# SMALL_BCM.net
KiCad netlist of a schematic drawn in Altium Designer
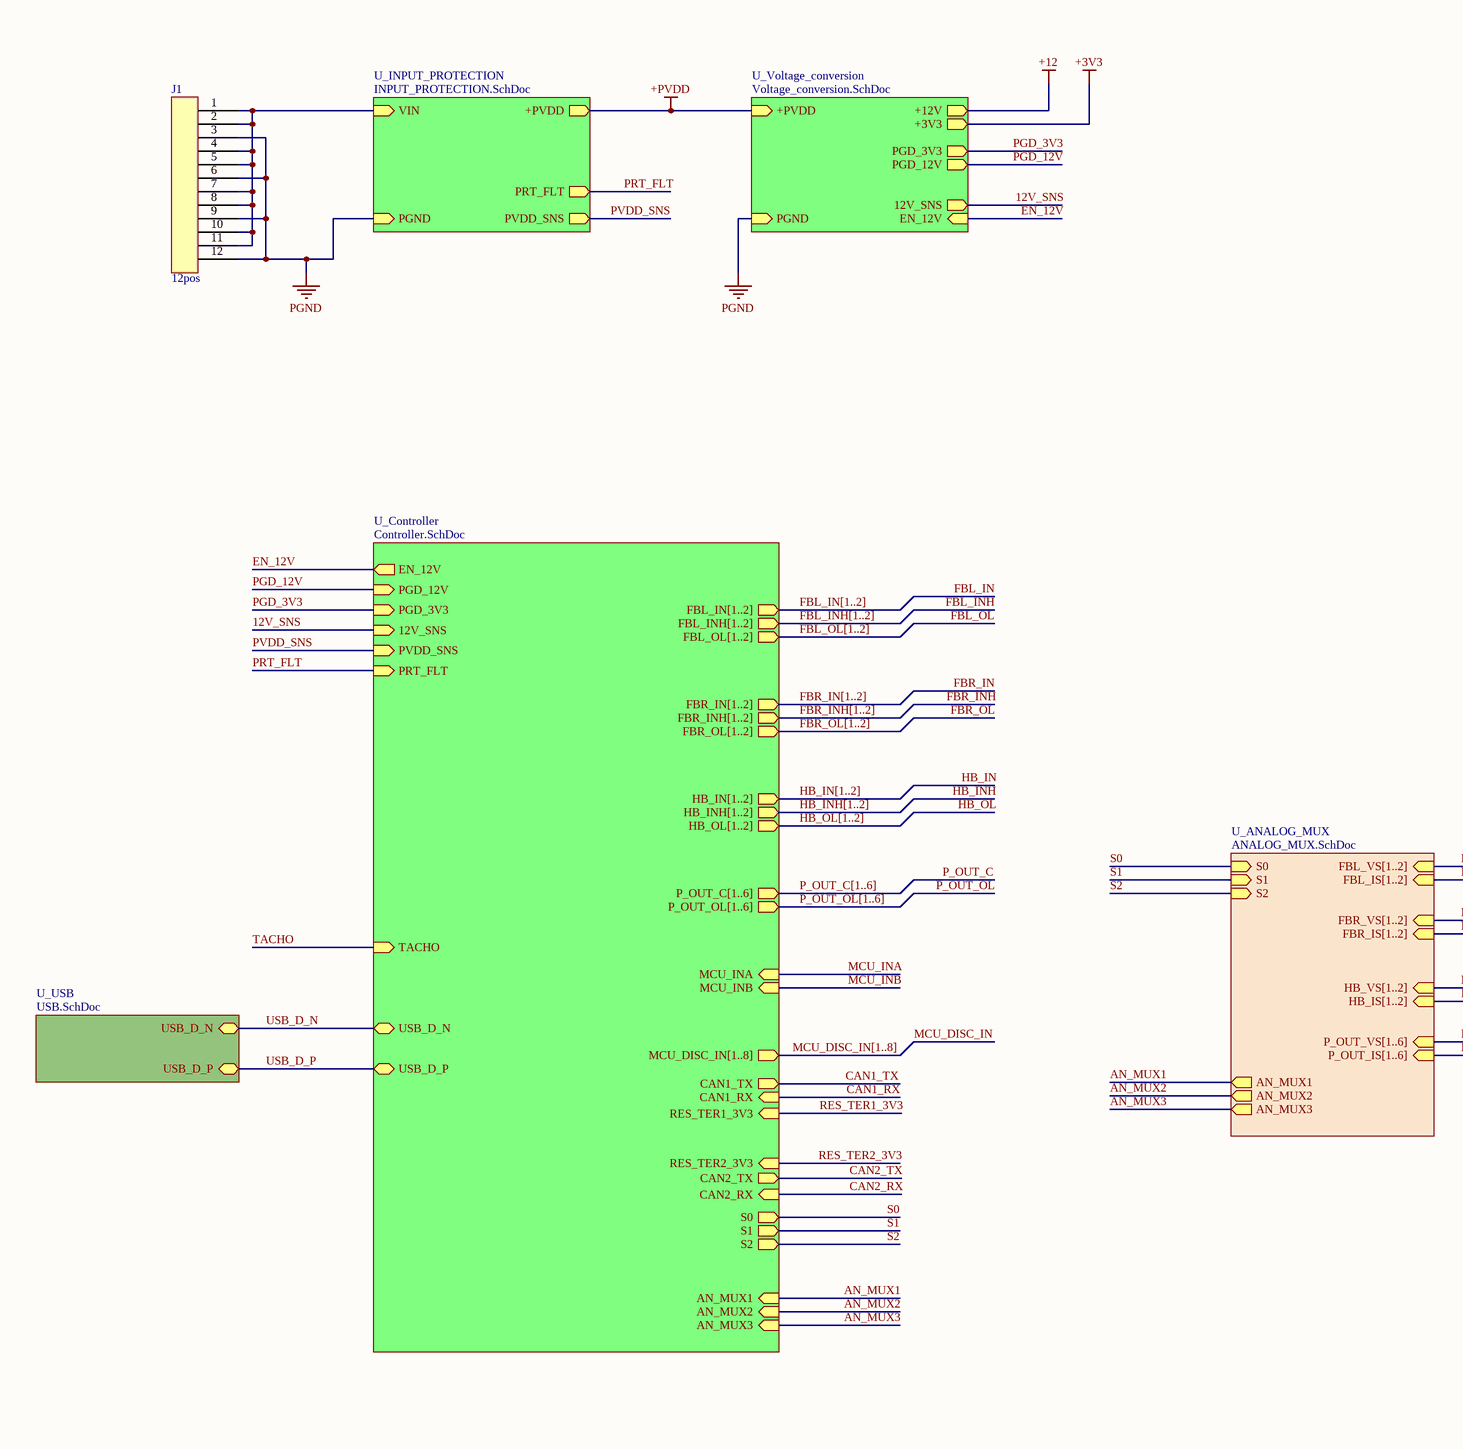
[diagram p0: SMALL_BCM.SchDoc, left]
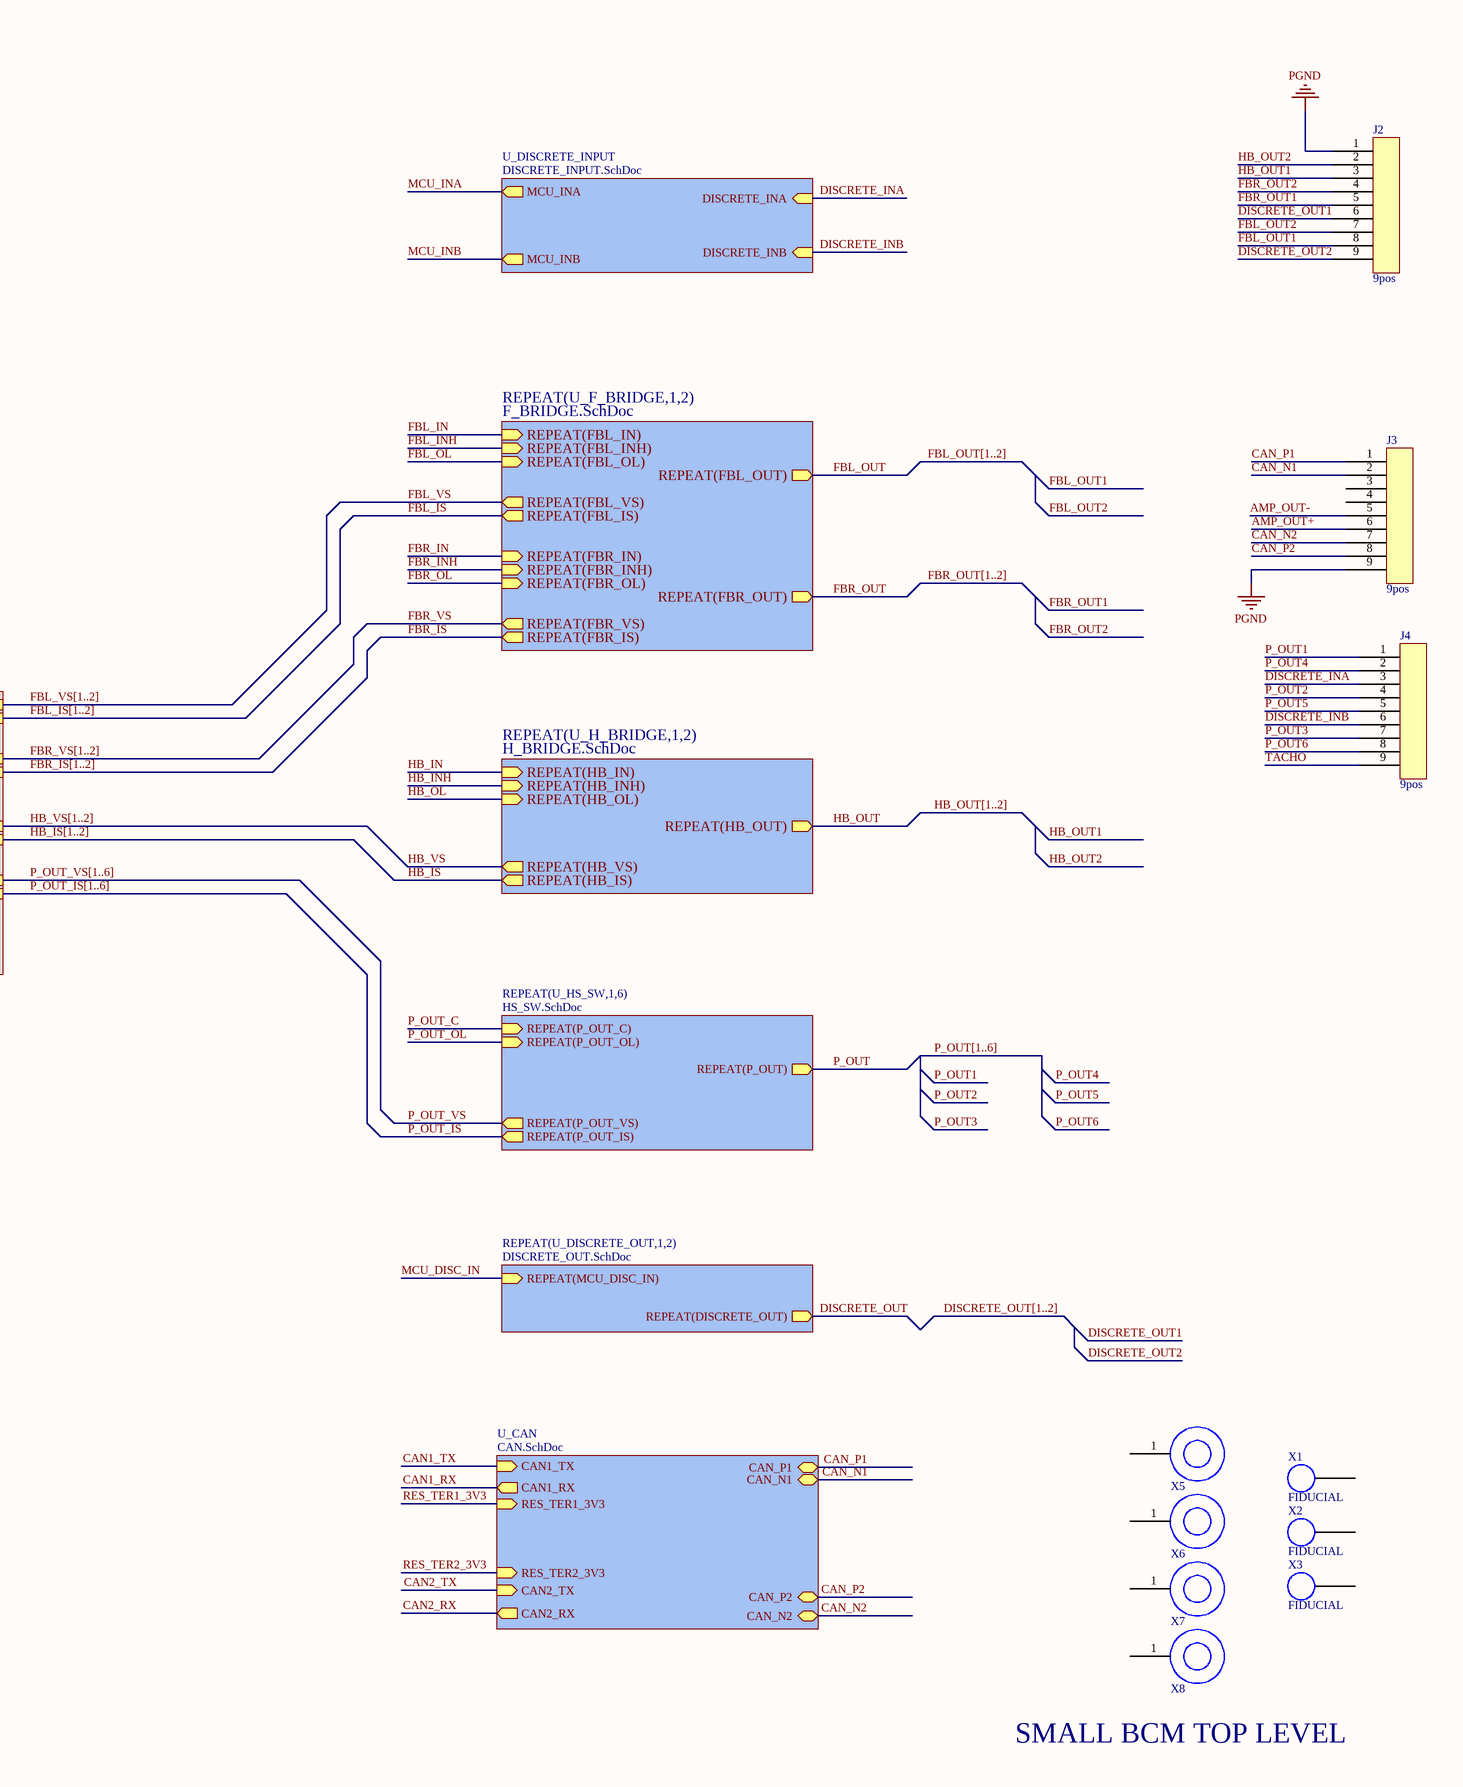
[diagram p1: SMALL_BCM.SchDoc, right]

(export (version "E")
  (design (tool "Eeschema 10.0.6"))
  (components
    (comp (ref "J1")
      (value "12pos")
      (footprint "9-966140-3")
      (description "CONN HEADER R/A 12POS 5MM")
      (libsource (lib "SMALL_BCM") (part "3x4_9-966140-3"))
    )
    (comp (ref "J2")
      (value "9pos")
      (footprint "9-966140-4")
      (description "CONN HEADER R/A 9POS 5MM")
      (libsource (lib "ECU") (part "3x4_9-966140-4"))
    )
    (comp (ref "J3")
      (value "9pos")
      (footprint "9-966140-4")
      (description "CONN HEADER R/A 9POS 5MM")
      (libsource (lib "ECU") (part "3x4_9-966140-4"))
    )
    (comp (ref "J4")
      (value "9pos")
      (footprint "9-966140-4")
      (description "CONN HEADER R/A 9POS 5MM")
      (libsource (lib "ECU") (part "3x4_9-966140-4"))
    )
    (comp (ref "X1")
      (value "FIDUCIAL")
      (footprint "FIDUCIAL")
      (description "FIDUCIAL 1mm")
      (libsource (lib "MISC_Library") (part "FIDUCIAL"))
    )
    (comp (ref "X2")
      (value "FIDUCIAL")
      (footprint "FIDUCIAL")
      (description "FIDUCIAL 1mm")
      (libsource (lib "MISC_Library") (part "FIDUCIAL"))
    )
    (comp (ref "X3")
      (value "FIDUCIAL")
      (footprint "FIDUCIAL")
      (description "FIDUCIAL 1mm")
      (libsource (lib "MISC_Library") (part "FIDUCIAL"))
    )
    (comp (ref "X5")
      (value "M3")
      (footprint "FIXING_M3")
      (description "FIXING HOLE M3")
      (libsource (lib "SCISONIC_DASHBOARD_V2") (part "FIXING_M3"))
    )
    (comp (ref "X6")
      (value "M3")
      (footprint "FIXING_M3")
      (description "FIXING HOLE M3")
      (libsource (lib "SCISONIC_DASHBOARD_V2") (part "FIXING_M3"))
    )
    (comp (ref "X7")
      (value "M3")
      (footprint "FIXING_M3")
      (description "FIXING HOLE M3")
      (libsource (lib "SCISONIC_DASHBOARD_V2") (part "FIXING_M3"))
    )
    (comp (ref "X8")
      (value "M3")
      (footprint "FIXING_M3")
      (description "FIXING HOLE M3")
      (libsource (lib "SCISONIC_DASHBOARD_V2") (part "FIXING_M3"))
    )
  )
  (nets
    (net (code "68") (name "/AMP_OUT+") (class "Default") (node (ref "J3") (pin "6") (pintype "passive")))
    (net (code "69") (name "/AMP_OUT-") (class "Default") (node (ref "J3") (pin "5") (pintype "passive")))
    (net (code "77") (name "/CAN_N1") (class "Default") (node (ref "J3") (pin "2") (pintype "passive")))
    (net (code "78") (name "/CAN_N2") (class "Default") (node (ref "J3") (pin "7") (pintype "passive")))
    (net (code "79") (name "/CAN_P1") (class "Default") (node (ref "J3") (pin "1") (pintype "passive")))
    (net (code "80") (name "/CAN_P2") (class "Default") (node (ref "J3") (pin "8") (pintype "passive")))
    (net (code "81") (name "/DISCRETE_INA") (class "Default") (node (ref "J4") (pin "3") (pintype "passive")))
    (net (code "82") (name "/DISCRETE_INB") (class "Default") (node (ref "J4") (pin "6") (pintype "passive")))
    (net (code "84") (name "/DISCRETE_OUT1") (class "Default")
      (node (ref "J2") (pin "6") (pintype "passive"))
    )
    (net (code "85") (name "/DISCRETE_OUT2") (class "Default")
      (node (ref "J2") (pin "9") (pintype "passive"))
    )
    (net (code "97") (name "/FBL_OUT1") (class "Default") (node (ref "J2") (pin "8") (pintype "passive")))
    (net (code "98") (name "/FBL_OUT2") (class "Default") (node (ref "J2") (pin "7") (pintype "passive")))
    (net (code "111") (name "/FBR_OUT1") (class "Default") (node (ref "J2") (pin "5") (pintype "passive")))
    (net (code "112") (name "/FBR_OUT2") (class "Default") (node (ref "J2") (pin "4") (pintype "passive")))
    (net (code "125") (name "/HB_OUT1") (class "Default") (node (ref "J2") (pin "3") (pintype "passive")))
    (net (code "126") (name "/HB_OUT2") (class "Default") (node (ref "J2") (pin "2") (pintype "passive")))
    (net (code "139") (name "/P_OUT1") (class "Default") (node (ref "J4") (pin "1") (pintype "passive")))
    (net (code "140") (name "/P_OUT2") (class "Default") (node (ref "J4") (pin "4") (pintype "passive")))
    (net (code "141") (name "/P_OUT3") (class "Default") (node (ref "J4") (pin "7") (pintype "passive")))
    (net (code "142") (name "/P_OUT4") (class "Default") (node (ref "J4") (pin "2") (pintype "passive")))
    (net (code "143") (name "/P_OUT5") (class "Default") (node (ref "J4") (pin "5") (pintype "passive")))
    (net (code "144") (name "/P_OUT6") (class "Default") (node (ref "J4") (pin "8") (pintype "passive")))
    (net (code "159") (name "/TACHO") (class "Default") (node (ref "J4") (pin "9") (pintype "passive")))
    (net (code "162") (name "/VIN") (class "Default")
      (node (ref "J1") (pin "1") (pintype "passive"))
      (node (ref "J1") (pin "10") (pintype "passive"))
      (node (ref "J1") (pin "11") (pintype "passive"))
      (node (ref "J1") (pin "2") (pintype "passive"))
      (node (ref "J1") (pin "4") (pintype "passive"))
      (node (ref "J1") (pin "5") (pintype "passive"))
      (node (ref "J1") (pin "7") (pintype "passive"))
      (node (ref "J1") (pin "8") (pintype "passive"))
    )
    (net (code "163") (name "PGND") (class "Default")
      (node (ref "J1") (pin "12") (pintype "passive"))
      (node (ref "J1") (pin "3") (pintype "passive"))
      (node (ref "J1") (pin "6") (pintype "passive"))
      (node (ref "J1") (pin "9") (pintype "passive"))
      (node (ref "J2") (pin "1") (pintype "passive"))
      (node (ref "J3") (pin "9") (pintype "passive"))
    )
    (net (code "164") (name "unconnected-(J3-Pad3)") (class "Default")
      (node (ref "J3") (pin "3") (pintype "passive"))
    )
    (net (code "165") (name "unconnected-(J3-Pad4)") (class "Default")
      (node (ref "J3") (pin "4") (pintype "passive"))
    )
    (net (code "166") (name "unconnected-(X1-Pad1)") (class "Default")
      (node (ref "X1") (pin "1") (pinfunction "1_1") (pintype "passive"))
    )
    (net (code "167") (name "unconnected-(X2-Pad1)") (class "Default")
      (node (ref "X2") (pin "1") (pinfunction "1_1") (pintype "passive"))
    )
    (net (code "168") (name "unconnected-(X3-Pad1)") (class "Default")
      (node (ref "X3") (pin "1") (pinfunction "1_1") (pintype "passive"))
    )
    (net (code "169") (name "unconnected-(X5-Pad1)") (class "Default")
      (node (ref "X5") (pin "1") (pinfunction "1_1") (pintype "passive"))
    )
    (net (code "170") (name "unconnected-(X6-Pad1)") (class "Default")
      (node (ref "X6") (pin "1") (pinfunction "1_1") (pintype "passive"))
    )
    (net (code "171") (name "unconnected-(X7-Pad1)") (class "Default")
      (node (ref "X7") (pin "1") (pinfunction "1_1") (pintype "passive"))
    )
    (net (code "172") (name "unconnected-(X8-Pad1)") (class "Default")
      (node (ref "X8") (pin "1") (pinfunction "1_1") (pintype "passive"))
    )
  )
)
